# Monotron-002.net
KiCad netlist of a schematic drawn in EAGLE
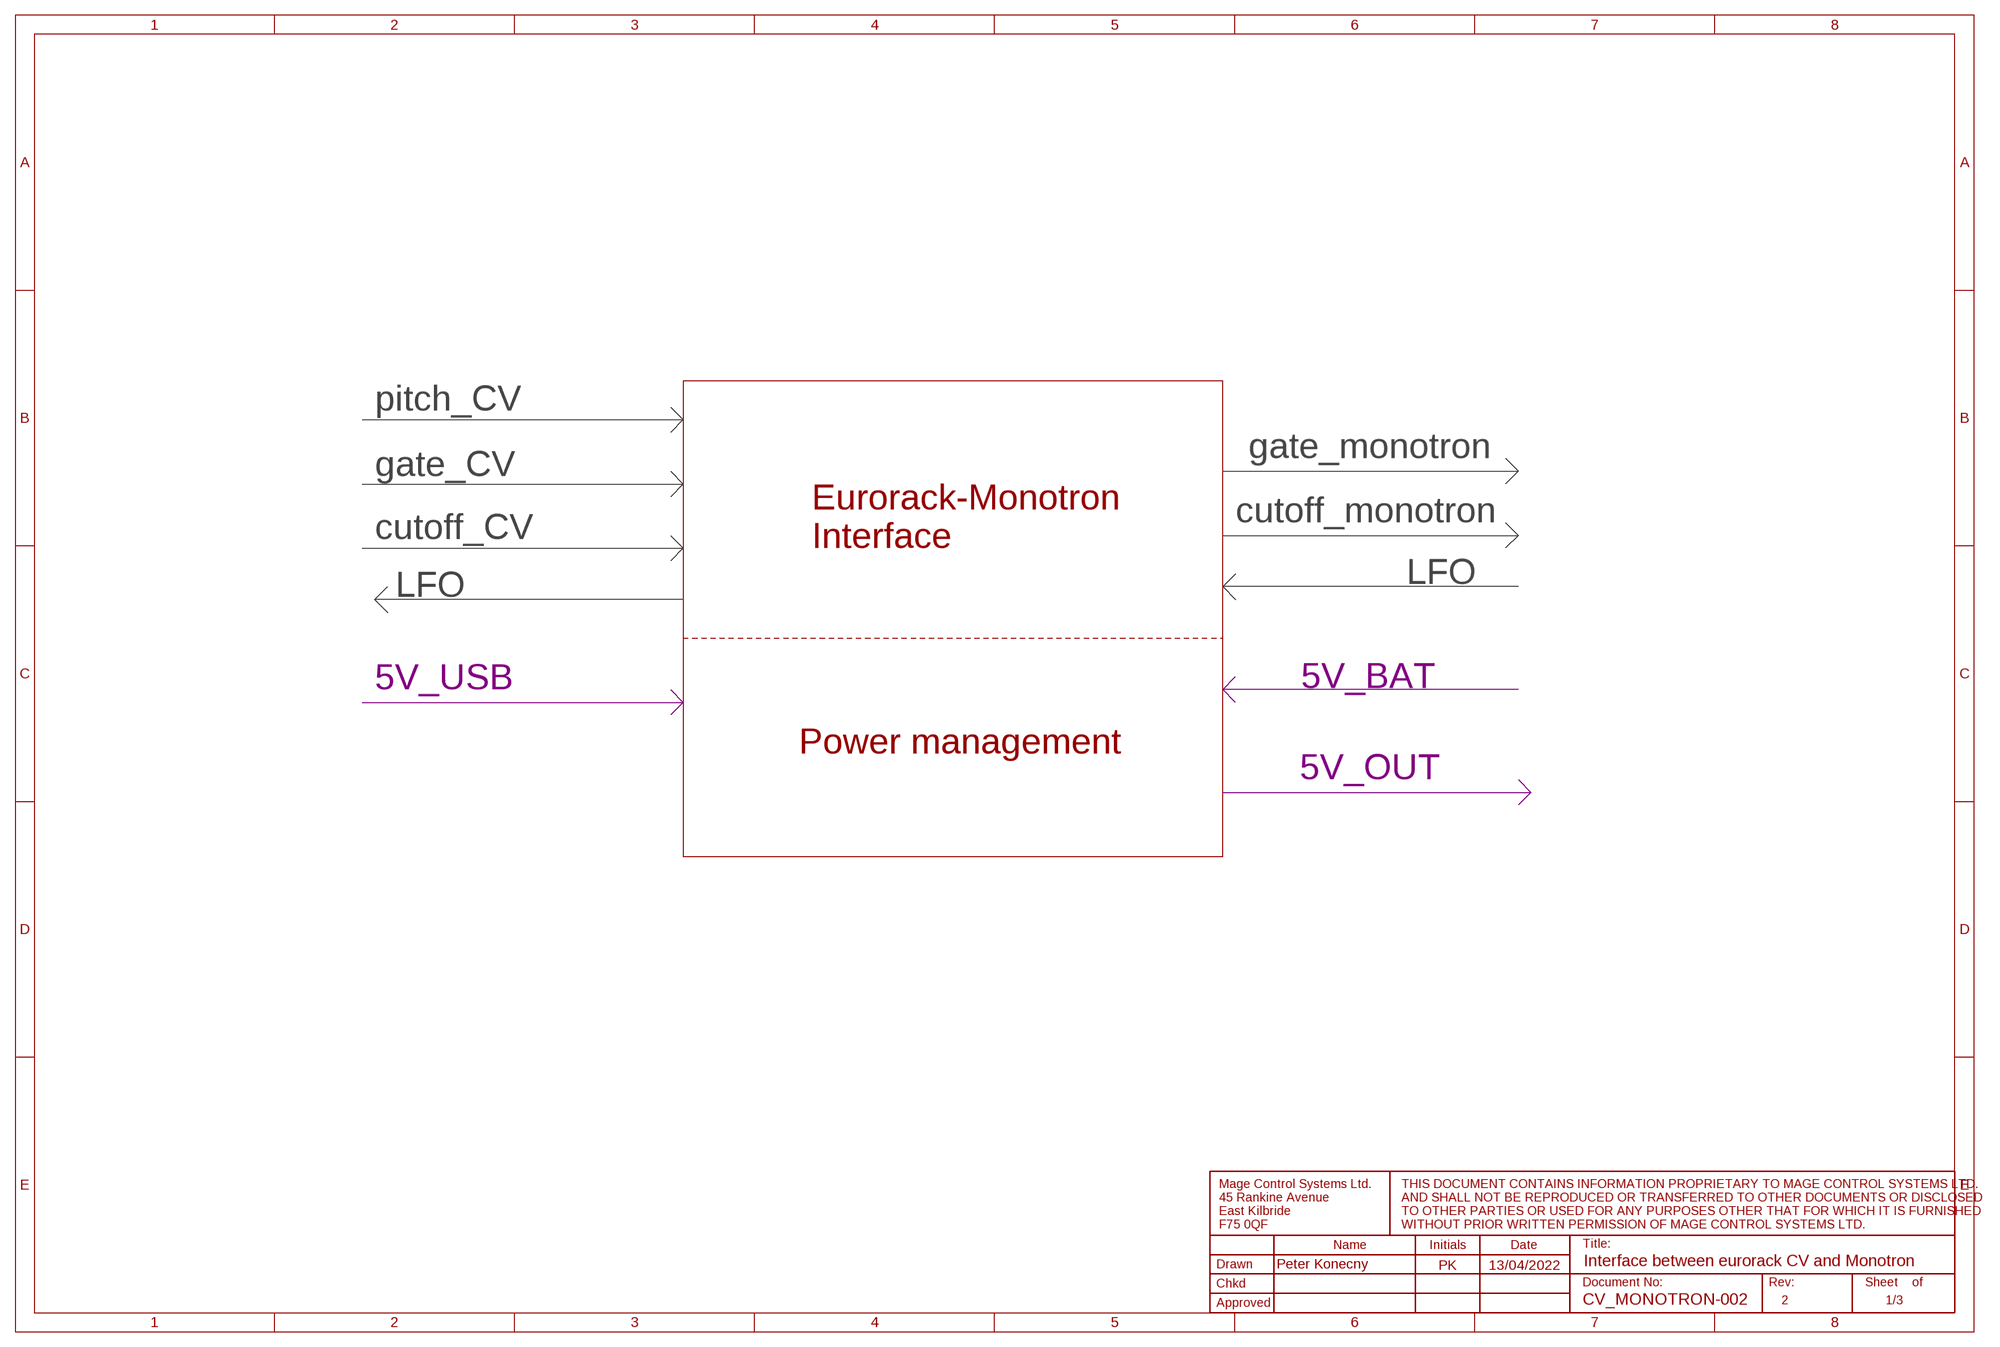
[diagram p0: schematic, sheet 1]
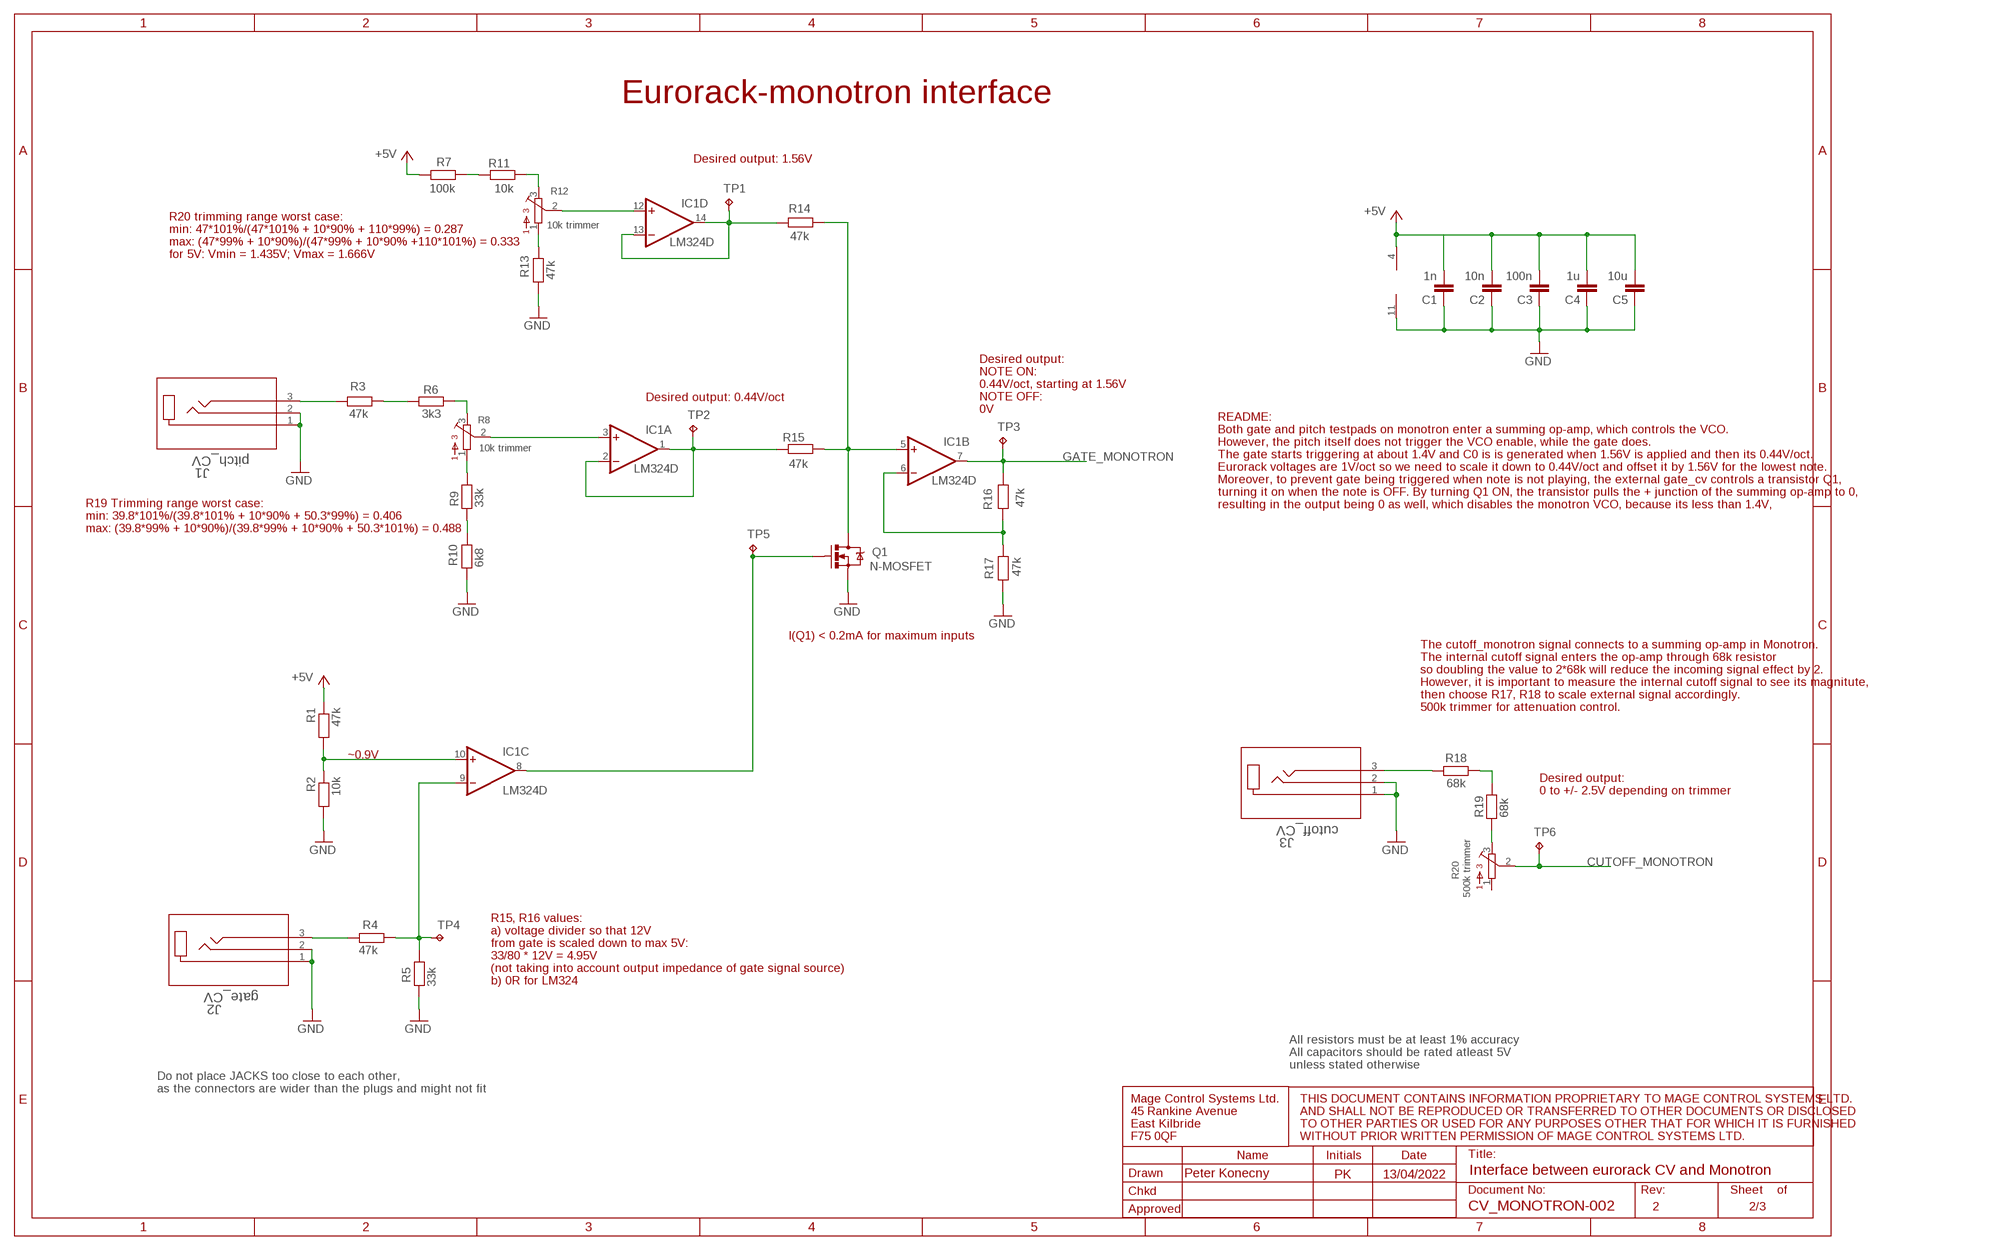
[diagram p1: schematic, sheet 2]
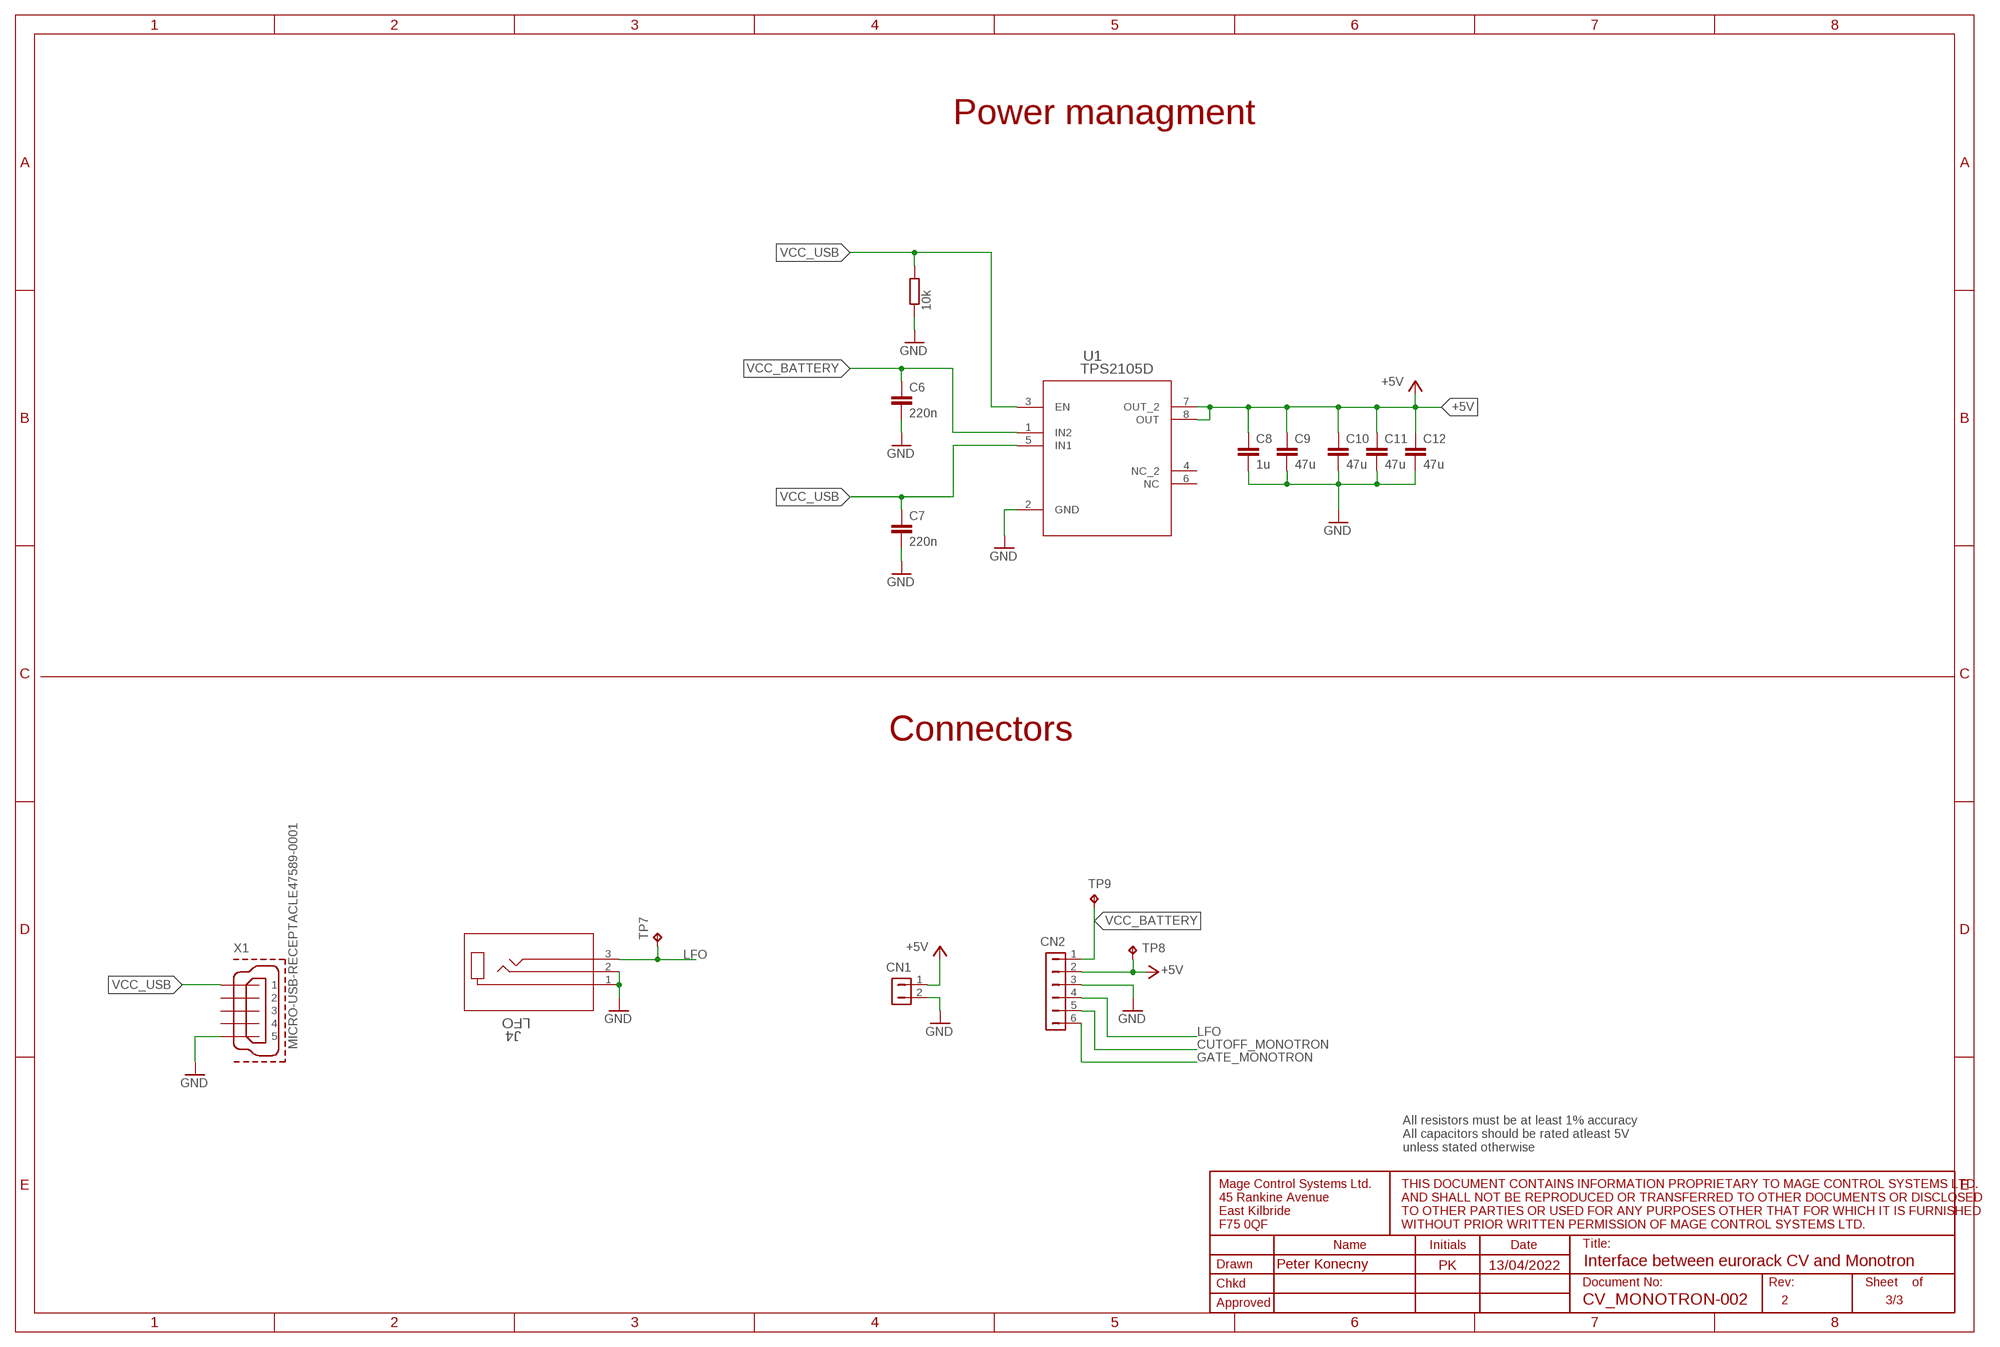
[diagram p2: schematic, sheet 3]

(export (version "E")
  (design (tool "Eeschema 10.0.6"))
  (components
    (comp (ref "C1")
      (value "1n")
      (footprint "eagle-import:C0603")
      (libsource (lib "eagle-import") (part "C-EUC0603"))
    )
    (comp (ref "C2")
      (value "10n")
      (footprint "eagle-import:C0603")
      (libsource (lib "eagle-import") (part "C-EUC0603"))
    )
    (comp (ref "C3")
      (value "100n")
      (footprint "eagle-import:C0603")
      (libsource (lib "eagle-import") (part "C-EUC0603"))
    )
    (comp (ref "C4")
      (value "1u")
      (footprint "eagle-import:C0603")
      (libsource (lib "eagle-import") (part "C-EUC0603"))
    )
    (comp (ref "C5")
      (value "10u")
      (footprint "eagle-import:C0805")
      (libsource (lib "eagle-import") (part "C-EUC0805"))
    )
    (comp (ref "IC1")
      (value "LM324D")
      (footprint "eagle-import:SO14")
      (libsource (lib "eagle-import") (part "LM324D"))
    )
    (comp (ref "J1")
      (value "pitch_CV")
      (footprint "eagle-import:STX-3000_KYC")
      (fields
        (field (name "MANUFACTURER_PART_NUMBER") "STX-3000")
        (field (name "COPYRIGHT") "Copyright (C) 2022 Ultra Librarian. All rights reserved.")
      )
      (libsource (lib "eagle-import") (part "STX-3000"))
    )
    (comp (ref "J2")
      (value "gate_CV")
      (footprint "eagle-import:STX-3000_KYC")
      (fields
        (field (name "MANUFACTURER_PART_NUMBER") "STX-3000")
        (field (name "COPYRIGHT") "Copyright (C) 2022 Ultra Librarian. All rights reserved.")
      )
      (libsource (lib "eagle-import") (part "STX-3000"))
    )
    (comp (ref "J3")
      (value "cutoff_CV")
      (footprint "eagle-import:STX-3000_KYC")
      (fields
        (field (name "MANUFACTURER_PART_NUMBER") "STX-3000")
        (field (name "COPYRIGHT") "Copyright (C) 2022 Ultra Librarian. All rights reserved.")
      )
      (libsource (lib "eagle-import") (part "STX-3000"))
    )
    (comp (ref "Q1")
      (value "N-MOSFET")
      (footprint "eagle-import:SOT23-3")
      (libsource (lib "eagle-import") (part "MOSFET-NCHANNELAO3404A"))
    )
    (comp (ref "R1")
      (value "47k")
      (footprint "eagle-import:R0603")
      (libsource (lib "eagle-import") (part "R-EUR0603"))
    )
    (comp (ref "R2")
      (value "10k")
      (footprint "eagle-import:R0603")
      (libsource (lib "eagle-import") (part "R-EUR0603"))
    )
    (comp (ref "R3")
      (value "47k")
      (footprint "eagle-import:R0603")
      (libsource (lib "eagle-import") (part "R-EUR0603"))
    )
    (comp (ref "R4")
      (value "47k")
      (footprint "eagle-import:R0603")
      (libsource (lib "eagle-import") (part "R-EUR0603"))
    )
    (comp (ref "R5")
      (value "33k")
      (footprint "eagle-import:R0603")
      (libsource (lib "eagle-import") (part "R-EUR0603"))
    )
    (comp (ref "R6")
      (value "3k3")
      (footprint "eagle-import:R0603")
      (libsource (lib "eagle-import") (part "R-EUR0603"))
    )
    (comp (ref "R7")
      (value "100k")
      (footprint "eagle-import:R0603")
      (libsource (lib "eagle-import") (part "R-EUR0603"))
    )
    (comp (ref "R8")
      (value "10k trimmer")
      (footprint "eagle-import:3362R")
      (libsource (lib "eagle-import") (part "3362R"))
    )
    (comp (ref "R9")
      (value "33k")
      (footprint "eagle-import:R0603")
      (libsource (lib "eagle-import") (part "R-EUR0603"))
    )
    (comp (ref "R10")
      (value "6k8")
      (footprint "eagle-import:R0603")
      (libsource (lib "eagle-import") (part "R-EUR0603"))
    )
    (comp (ref "R11")
      (value "10k")
      (footprint "eagle-import:R0603")
      (libsource (lib "eagle-import") (part "R-EUR0603"))
    )
    (comp (ref "R12")
      (value "10k trimmer")
      (footprint "eagle-import:3362R")
      (libsource (lib "eagle-import") (part "3362R"))
    )
    (comp (ref "R13")
      (value "47k")
      (footprint "eagle-import:R0603")
      (libsource (lib "eagle-import") (part "R-EUR0603"))
    )
    (comp (ref "R14")
      (value "47k")
      (footprint "eagle-import:R0603")
      (libsource (lib "eagle-import") (part "R-EUR0603"))
    )
    (comp (ref "R15")
      (value "47k")
      (footprint "eagle-import:R0603")
      (libsource (lib "eagle-import") (part "R-EUR0603"))
    )
    (comp (ref "R16")
      (value "47k")
      (footprint "eagle-import:R0603")
      (libsource (lib "eagle-import") (part "R-EUR0603"))
    )
    (comp (ref "R17")
      (value "47k")
      (footprint "eagle-import:R0603")
      (libsource (lib "eagle-import") (part "R-EUR0603"))
    )
    (comp (ref "R18")
      (value "68k")
      (footprint "eagle-import:R0603")
      (libsource (lib "eagle-import") (part "R-EUR0603"))
    )
    (comp (ref "R19")
      (value "68k")
      (footprint "eagle-import:R0603")
      (libsource (lib "eagle-import") (part "R-EUR0603"))
    )
    (comp (ref "R20")
      (value "500k trimmer")
      (footprint "eagle-import:3362R")
      (libsource (lib "eagle-import") (part "3362R"))
    )
    (comp (ref "TP1")
      (value "TPB1,27")
      (footprint "eagle-import:B1,27")
      (libsource (lib "eagle-import") (part "TPB1,27"))
    )
    (comp (ref "TP2")
      (value "TPB1,27")
      (footprint "eagle-import:B1,27")
      (libsource (lib "eagle-import") (part "TPB1,27"))
    )
    (comp (ref "TP3")
      (value "TPB1,27")
      (footprint "eagle-import:B1,27")
      (libsource (lib "eagle-import") (part "TPB1,27"))
    )
    (comp (ref "TP4")
      (value "TPB1,27")
      (footprint "eagle-import:B1,27")
      (libsource (lib "eagle-import") (part "TPB1,27"))
    )
    (comp (ref "TP5")
      (value "TPB1,27")
      (footprint "eagle-import:B1,27")
      (libsource (lib "eagle-import") (part "TPB1,27"))
    )
    (comp (ref "TP6")
      (value "TPB1,27")
      (footprint "eagle-import:B1,27")
      (libsource (lib "eagle-import") (part "TPB1,27"))
    )
    (comp (ref "C6")
      (value "220n")
      (footprint "eagle-import:C0603")
      (libsource (lib "eagle-import") (part "rcl_334_C-EUC0603"))
    )
    (comp (ref "C7")
      (value "220n")
      (footprint "eagle-import:C0603")
      (libsource (lib "eagle-import") (part "rcl_334_C-EUC0603"))
    )
    (comp (ref "C8")
      (value "1u")
      (footprint "eagle-import:C0603")
      (libsource (lib "eagle-import") (part "rcl_334_C-EUC0603"))
    )
    (comp (ref "C9")
      (value "47u")
      (footprint "eagle-import:C0805")
      (libsource (lib "eagle-import") (part "rcl_334_C-EUC0805"))
    )
    (comp (ref "C10")
      (value "47u")
      (footprint "eagle-import:C0805")
      (libsource (lib "eagle-import") (part "rcl_334_C-EUC0805"))
    )
    (comp (ref "C11")
      (value "47u")
      (footprint "eagle-import:C0805")
      (libsource (lib "eagle-import") (part "rcl_334_C-EUC0805"))
    )
    (comp (ref "C12")
      (value "47u")
      (footprint "eagle-import:C0805")
      (libsource (lib "eagle-import") (part "rcl_334_C-EUC0805"))
    )
    (comp (ref "CN1")
      (value "HDR-1X2-SIP-100")
      (footprint "eagle-import:SIP-100-2V")
      (libsource (lib "eagle-import") (part "HDR-1X2-SIP-100"))
    )
    (comp (ref "CN2")
      (value "HDR-1X6-SIP-100")
      (footprint "eagle-import:SIP-100-6V")
      (libsource (lib "eagle-import") (part "HDR-1X6-SIP-100"))
    )
    (comp (ref "J4")
      (value "LFO")
      (footprint "eagle-import:STX-3000_KYC")
      (fields
        (field (name "MANUFACTURER_PART_NUMBER") "STX-3000")
        (field (name "COPYRIGHT") "Copyright (C) 2022 Ultra Librarian. All rights reserved.")
      )
      (libsource (lib "eagle-import") (part "STX-3000"))
    )
    (comp (ref "R21")
      (value "10k")
      (footprint "eagle-import:R0603")
      (libsource (lib "eagle-import") (part "R-EU_R0603"))
    )
    (comp (ref "TP7")
      (value "TPB1,27")
      (footprint "eagle-import:B1,27")
      (libsource (lib "eagle-import") (part "TPB1,27"))
    )
    (comp (ref "TP8")
      (value "TPB1,27")
      (footprint "eagle-import:B1,27")
      (libsource (lib "eagle-import") (part "TPB1,27"))
    )
    (comp (ref "TP9")
      (value "TPB1,27")
      (footprint "eagle-import:B1,27")
      (libsource (lib "eagle-import") (part "TPB1,27"))
    )
    (comp (ref "U1")
      (value "TPS2105D")
      (footprint "eagle-import:D8")
      (fields (field (name "COPYRIGHT") "Copyright (C) 2022 Ultra Librarian. All rights reserved."))
      (libsource (lib "eagle-import") (part "TPS2105D"))
    )
    (comp (ref "X1")
      (value "MICRO-USB-RECEPTACLE47589-0001")
      (footprint "eagle-import:47589-0001")
      (libsource (lib "eagle-import") (part "MICRO-USB-RECEPTACLE47589-0001"))
    )
  )
  (nets
    (net (code "1") (name "+5V") (class "Default")
      (node (ref "C1") (pin "2") (pinfunction "2_2") (pintype "passive"))
      (node (ref "C10") (pin "1") (pinfunction "1_1") (pintype "passive"))
      (node (ref "C11") (pin "1") (pinfunction "1_1") (pintype "passive"))
      (node (ref "C12") (pin "1") (pinfunction "1_1") (pintype "passive"))
      (node (ref "C2") (pin "2") (pinfunction "2_2") (pintype "passive"))
      (node (ref "C3") (pin "2") (pinfunction "2_2") (pintype "passive"))
      (node (ref "C4") (pin "2") (pinfunction "2_2") (pintype "passive"))
      (node (ref "C5") (pin "2") (pinfunction "2_2") (pintype "passive"))
      (node (ref "C8") (pin "1") (pinfunction "1_1") (pintype "passive"))
      (node (ref "C9") (pin "1") (pinfunction "1_1") (pintype "passive"))
      (node (ref "CN1") (pin "1") (pinfunction "1_1") (pintype "passive"))
      (node (ref "CN2") (pin "2") (pinfunction "2_2") (pintype "passive"))
      (node (ref "IC1") (pin "4") (pinfunction "V+_4") (pintype "power_in"))
      (node (ref "R1") (pin "1") (pinfunction "1_1") (pintype "passive"))
      (node (ref "R7") (pin "2") (pinfunction "2_2") (pintype "passive"))
      (node (ref "TP8") (pin "TP") (pinfunction "TP_TP") (pintype "input"))
      (node (ref "U1") (pin "7") (pinfunction "OUT_2_7") (pintype "output"))
      (node (ref "U1") (pin "8") (pinfunction "OUT_8") (pintype "output"))
    )
    (net (code "2") (name "CUTOFF_MONOTRON") (class "Default")
      (node (ref "CN2") (pin "5") (pinfunction "5_5") (pintype "passive"))
      (node (ref "R20") (pin "2") (pinfunction "2_2") (pintype "passive"))
      (node (ref "TP6") (pin "TP") (pinfunction "TP_TP") (pintype "input"))
    )
    (net (code "3") (name "GATE_MONOTRON") (class "Default")
      (node (ref "CN2") (pin "6") (pinfunction "6_6") (pintype "passive"))
      (node (ref "IC1") (pin "7") (pinfunction "OUT_7") (pintype "output"))
      (node (ref "R16") (pin "1") (pinfunction "1_1") (pintype "passive"))
      (node (ref "TP3") (pin "TP") (pinfunction "TP_TP") (pintype "input"))
    )
    (net (code "4") (name "GND") (class "Default")
      (node (ref "C1") (pin "1") (pinfunction "1_1") (pintype "passive"))
      (node (ref "C10") (pin "2") (pinfunction "2_2") (pintype "passive"))
      (node (ref "C11") (pin "2") (pinfunction "2_2") (pintype "passive"))
      (node (ref "C12") (pin "2") (pinfunction "2_2") (pintype "passive"))
      (node (ref "C2") (pin "1") (pinfunction "1_1") (pintype "passive"))
      (node (ref "C3") (pin "1") (pinfunction "1_1") (pintype "passive"))
      (node (ref "C4") (pin "1") (pinfunction "1_1") (pintype "passive"))
      (node (ref "C5") (pin "1") (pinfunction "1_1") (pintype "passive"))
      (node (ref "C6") (pin "2") (pinfunction "2_2") (pintype "passive"))
      (node (ref "C7") (pin "2") (pinfunction "2_2") (pintype "passive"))
      (node (ref "C8") (pin "2") (pinfunction "2_2") (pintype "passive"))
      (node (ref "C9") (pin "2") (pinfunction "2_2") (pintype "passive"))
      (node (ref "CN1") (pin "2") (pinfunction "2_2") (pintype "passive"))
      (node (ref "CN2") (pin "3") (pinfunction "3_3") (pintype "passive"))
      (node (ref "IC1") (pin "11") (pinfunction "V-_11") (pintype "power_in"))
      (node (ref "J1") (pin "1") (pinfunction "1_1") (pintype "passive"))
      (node (ref "J1") (pin "2") (pinfunction "2_2") (pintype "passive"))
      (node (ref "J2") (pin "1") (pinfunction "1_1") (pintype "passive"))
      (node (ref "J2") (pin "2") (pinfunction "2_2") (pintype "passive"))
      (node (ref "J3") (pin "1") (pinfunction "1_1") (pintype "passive"))
      (node (ref "J3") (pin "2") (pinfunction "2_2") (pintype "passive"))
      (node (ref "J4") (pin "1") (pinfunction "1_1") (pintype "passive"))
      (node (ref "J4") (pin "2") (pinfunction "2_2") (pintype "passive"))
      (node (ref "Q1") (pin "2") (pinfunction "S_2") (pintype "passive"))
      (node (ref "R10") (pin "1") (pinfunction "1_1") (pintype "passive"))
      (node (ref "R13") (pin "1") (pinfunction "1_1") (pintype "passive"))
      (node (ref "R17") (pin "2") (pinfunction "2_2") (pintype "passive"))
      (node (ref "R2") (pin "2") (pinfunction "2_2") (pintype "passive"))
      (node (ref "R21") (pin "1") (pinfunction "1_1") (pintype "passive"))
      (node (ref "R5") (pin "2") (pinfunction "2_2") (pintype "passive"))
      (node (ref "U1") (pin "2") (pinfunction "GND_2") (pintype "power_in"))
      (node (ref "X1") (pin "5") (pinfunction "5_5") (pintype "input"))
    )
    (net (code "5") (name "LFO") (class "Default")
      (node (ref "CN2") (pin "4") (pinfunction "4_4") (pintype "passive"))
      (node (ref "J4") (pin "3") (pinfunction "3_3") (pintype "passive"))
      (node (ref "TP7") (pin "TP") (pinfunction "TP_TP") (pintype "input"))
    )
    (net (code "6") (name "Net-(IC1A-+IN)") (class "Default")
      (node (ref "IC1") (pin "3") (pinfunction "+IN_3") (pintype "input"))
      (node (ref "R8") (pin "2") (pinfunction "2_2") (pintype "passive"))
    )
    (net (code "7") (name "Net-(IC1A--IN)") (class "Default")
      (node (ref "IC1") (pin "1") (pinfunction "OUT_1") (pintype "output"))
      (node (ref "IC1") (pin "2") (pinfunction "-IN_2") (pintype "input"))
      (node (ref "R15") (pin "2") (pinfunction "2_2") (pintype "passive"))
      (node (ref "TP2") (pin "TP") (pinfunction "TP_TP") (pintype "input"))
    )
    (net (code "8") (name "Net-(IC1B-+IN)") (class "Default")
      (node (ref "IC1") (pin "5") (pinfunction "+IN_5") (pintype "input"))
      (node (ref "Q1") (pin "3") (pinfunction "D_3") (pintype "passive"))
      (node (ref "R14") (pin "1") (pinfunction "1_1") (pintype "passive"))
      (node (ref "R15") (pin "1") (pinfunction "1_1") (pintype "passive"))
    )
    (net (code "9") (name "Net-(IC1B--IN)") (class "Default")
      (node (ref "IC1") (pin "6") (pinfunction "-IN_6") (pintype "input"))
      (node (ref "R16") (pin "2") (pinfunction "2_2") (pintype "passive"))
      (node (ref "R17") (pin "1") (pinfunction "1_1") (pintype "passive"))
    )
    (net (code "10") (name "Net-(IC1C-+IN)") (class "Default")
      (node (ref "IC1") (pin "10") (pinfunction "+IN_10") (pintype "input"))
      (node (ref "R1") (pin "2") (pinfunction "2_2") (pintype "passive"))
      (node (ref "R2") (pin "1") (pinfunction "1_1") (pintype "passive"))
    )
    (net (code "11") (name "Net-(IC1C--IN)") (class "Default")
      (node (ref "IC1") (pin "9") (pinfunction "-IN_9") (pintype "input"))
      (node (ref "R4") (pin "1") (pinfunction "1_1") (pintype "passive"))
      (node (ref "R5") (pin "1") (pinfunction "1_1") (pintype "passive"))
      (node (ref "TP4") (pin "TP") (pinfunction "TP_TP") (pintype "input"))
    )
    (net (code "12") (name "Net-(IC1C-OUT)") (class "Default")
      (node (ref "IC1") (pin "8") (pinfunction "OUT_8") (pintype "output"))
      (node (ref "Q1") (pin "1") (pinfunction "G_1") (pintype "passive"))
      (node (ref "TP5") (pin "TP") (pinfunction "TP_TP") (pintype "input"))
    )
    (net (code "13") (name "Net-(IC1D-+IN)") (class "Default")
      (node (ref "IC1") (pin "12") (pinfunction "+IN_12") (pintype "input"))
      (node (ref "R12") (pin "2") (pinfunction "2_2") (pintype "passive"))
    )
    (net (code "14") (name "Net-(IC1D--IN)") (class "Default")
      (node (ref "IC1") (pin "13") (pinfunction "-IN_13") (pintype "input"))
      (node (ref "IC1") (pin "14") (pinfunction "OUT_14") (pintype "output"))
      (node (ref "R14") (pin "2") (pinfunction "2_2") (pintype "passive"))
      (node (ref "TP1") (pin "TP") (pinfunction "TP_TP") (pintype "input"))
    )
    (net (code "15") (name "Net-(J1-Pad3)") (class "Default")
      (node (ref "J1") (pin "3") (pinfunction "3_3") (pintype "passive"))
      (node (ref "R3") (pin "1") (pinfunction "1_1") (pintype "passive"))
    )
    (net (code "16") (name "Net-(J2-Pad3)") (class "Default")
      (node (ref "J2") (pin "3") (pinfunction "3_3") (pintype "passive"))
      (node (ref "R4") (pin "2") (pinfunction "2_2") (pintype "passive"))
    )
    (net (code "17") (name "Net-(J3-Pad3)") (class "Default")
      (node (ref "J3") (pin "3") (pinfunction "3_3") (pintype "passive"))
      (node (ref "R18") (pin "2") (pinfunction "2_2") (pintype "passive"))
    )
    (net (code "18") (name "Net-(R3-Pad2)") (class "Default")
      (node (ref "R3") (pin "2") (pinfunction "2_2") (pintype "passive"))
      (node (ref "R6") (pin "2") (pinfunction "2_2") (pintype "passive"))
    )
    (net (code "19") (name "Net-(R6-Pad1)") (class "Default")
      (node (ref "R6") (pin "1") (pinfunction "1_1") (pintype "passive"))
      (node (ref "R8") (pin "3") (pinfunction "3_3") (pintype "passive"))
    )
    (net (code "20") (name "Net-(R8-Pad1)") (class "Default")
      (node (ref "R8") (pin "1") (pinfunction "1_1") (pintype "passive"))
      (node (ref "R9") (pin "2") (pinfunction "2_2") (pintype "passive"))
    )
    (net (code "21") (name "Net-(R10-Pad2)") (class "Default")
      (node (ref "R10") (pin "2") (pinfunction "2_2") (pintype "passive"))
      (node (ref "R9") (pin "1") (pinfunction "1_1") (pintype "passive"))
    )
    (net (code "22") (name "Net-(R11-Pad1)") (class "Default")
      (node (ref "R11") (pin "1") (pinfunction "1_1") (pintype "passive"))
      (node (ref "R12") (pin "3") (pinfunction "3_3") (pintype "passive"))
    )
    (net (code "23") (name "Net-(R11-Pad2)") (class "Default")
      (node (ref "R11") (pin "2") (pinfunction "2_2") (pintype "passive"))
      (node (ref "R7") (pin "1") (pinfunction "1_1") (pintype "passive"))
    )
    (net (code "24") (name "Net-(R12-Pad1)") (class "Default")
      (node (ref "R12") (pin "1") (pinfunction "1_1") (pintype "passive"))
      (node (ref "R13") (pin "2") (pinfunction "2_2") (pintype "passive"))
    )
    (net (code "25") (name "Net-(R18-Pad1)") (class "Default")
      (node (ref "R18") (pin "1") (pinfunction "1_1") (pintype "passive"))
      (node (ref "R19") (pin "2") (pinfunction "2_2") (pintype "passive"))
    )
    (net (code "26") (name "Net-(R19-Pad1)") (class "Default")
      (node (ref "R19") (pin "1") (pinfunction "1_1") (pintype "passive"))
      (node (ref "R20") (pin "3") (pinfunction "3_3") (pintype "passive"))
    )
    (net (code "27") (name "VCC_BATTERY") (class "Default")
      (node (ref "C6") (pin "1") (pinfunction "1_1") (pintype "passive"))
      (node (ref "CN2") (pin "1") (pinfunction "1_1") (pintype "passive"))
      (node (ref "TP9") (pin "TP") (pinfunction "TP_TP") (pintype "input"))
      (node (ref "U1") (pin "1") (pinfunction "IN2_1") (pintype "input"))
    )
    (net (code "28") (name "VCC_USB") (class "Default")
      (node (ref "C7") (pin "1") (pinfunction "1_1") (pintype "passive"))
      (node (ref "R21") (pin "2") (pinfunction "2_2") (pintype "passive"))
      (node (ref "U1") (pin "3") (pinfunction "EN_3") (pintype "input"))
      (node (ref "U1") (pin "5") (pinfunction "IN1_5") (pintype "input"))
      (node (ref "X1") (pin "1") (pinfunction "1_1") (pintype "input"))
    )
    (net (code "29") (name "unconnected-(R20-Pad1)") (class "Default")
      (node (ref "R20") (pin "1") (pinfunction "1_1") (pintype "passive"))
    )
    (net (code "30") (name "unconnected-(U1-NC-Pad6)") (class "Default")
      (node (ref "U1") (pin "6") (pinfunction "NC_6") (pintype "passive"))
    )
    (net (code "31") (name "unconnected-(U1-NC_2-Pad4)") (class "Default")
      (node (ref "U1") (pin "4") (pinfunction "NC_2_4") (pintype "passive"))
    )
    (net (code "32") (name "unconnected-(X1-Pad2)") (class "Default")
      (node (ref "X1") (pin "2") (pinfunction "2_2") (pintype "input"))
    )
    (net (code "33") (name "unconnected-(X1-Pad3)") (class "Default")
      (node (ref "X1") (pin "3") (pinfunction "3_3") (pintype "input"))
    )
    (net (code "34") (name "unconnected-(X1-Pad4)") (class "Default")
      (node (ref "X1") (pin "4") (pinfunction "4_4") (pintype "input"))
    )
  )
)
